# Rev_B.net
KiCad netlist of a schematic drawn in EAGLE
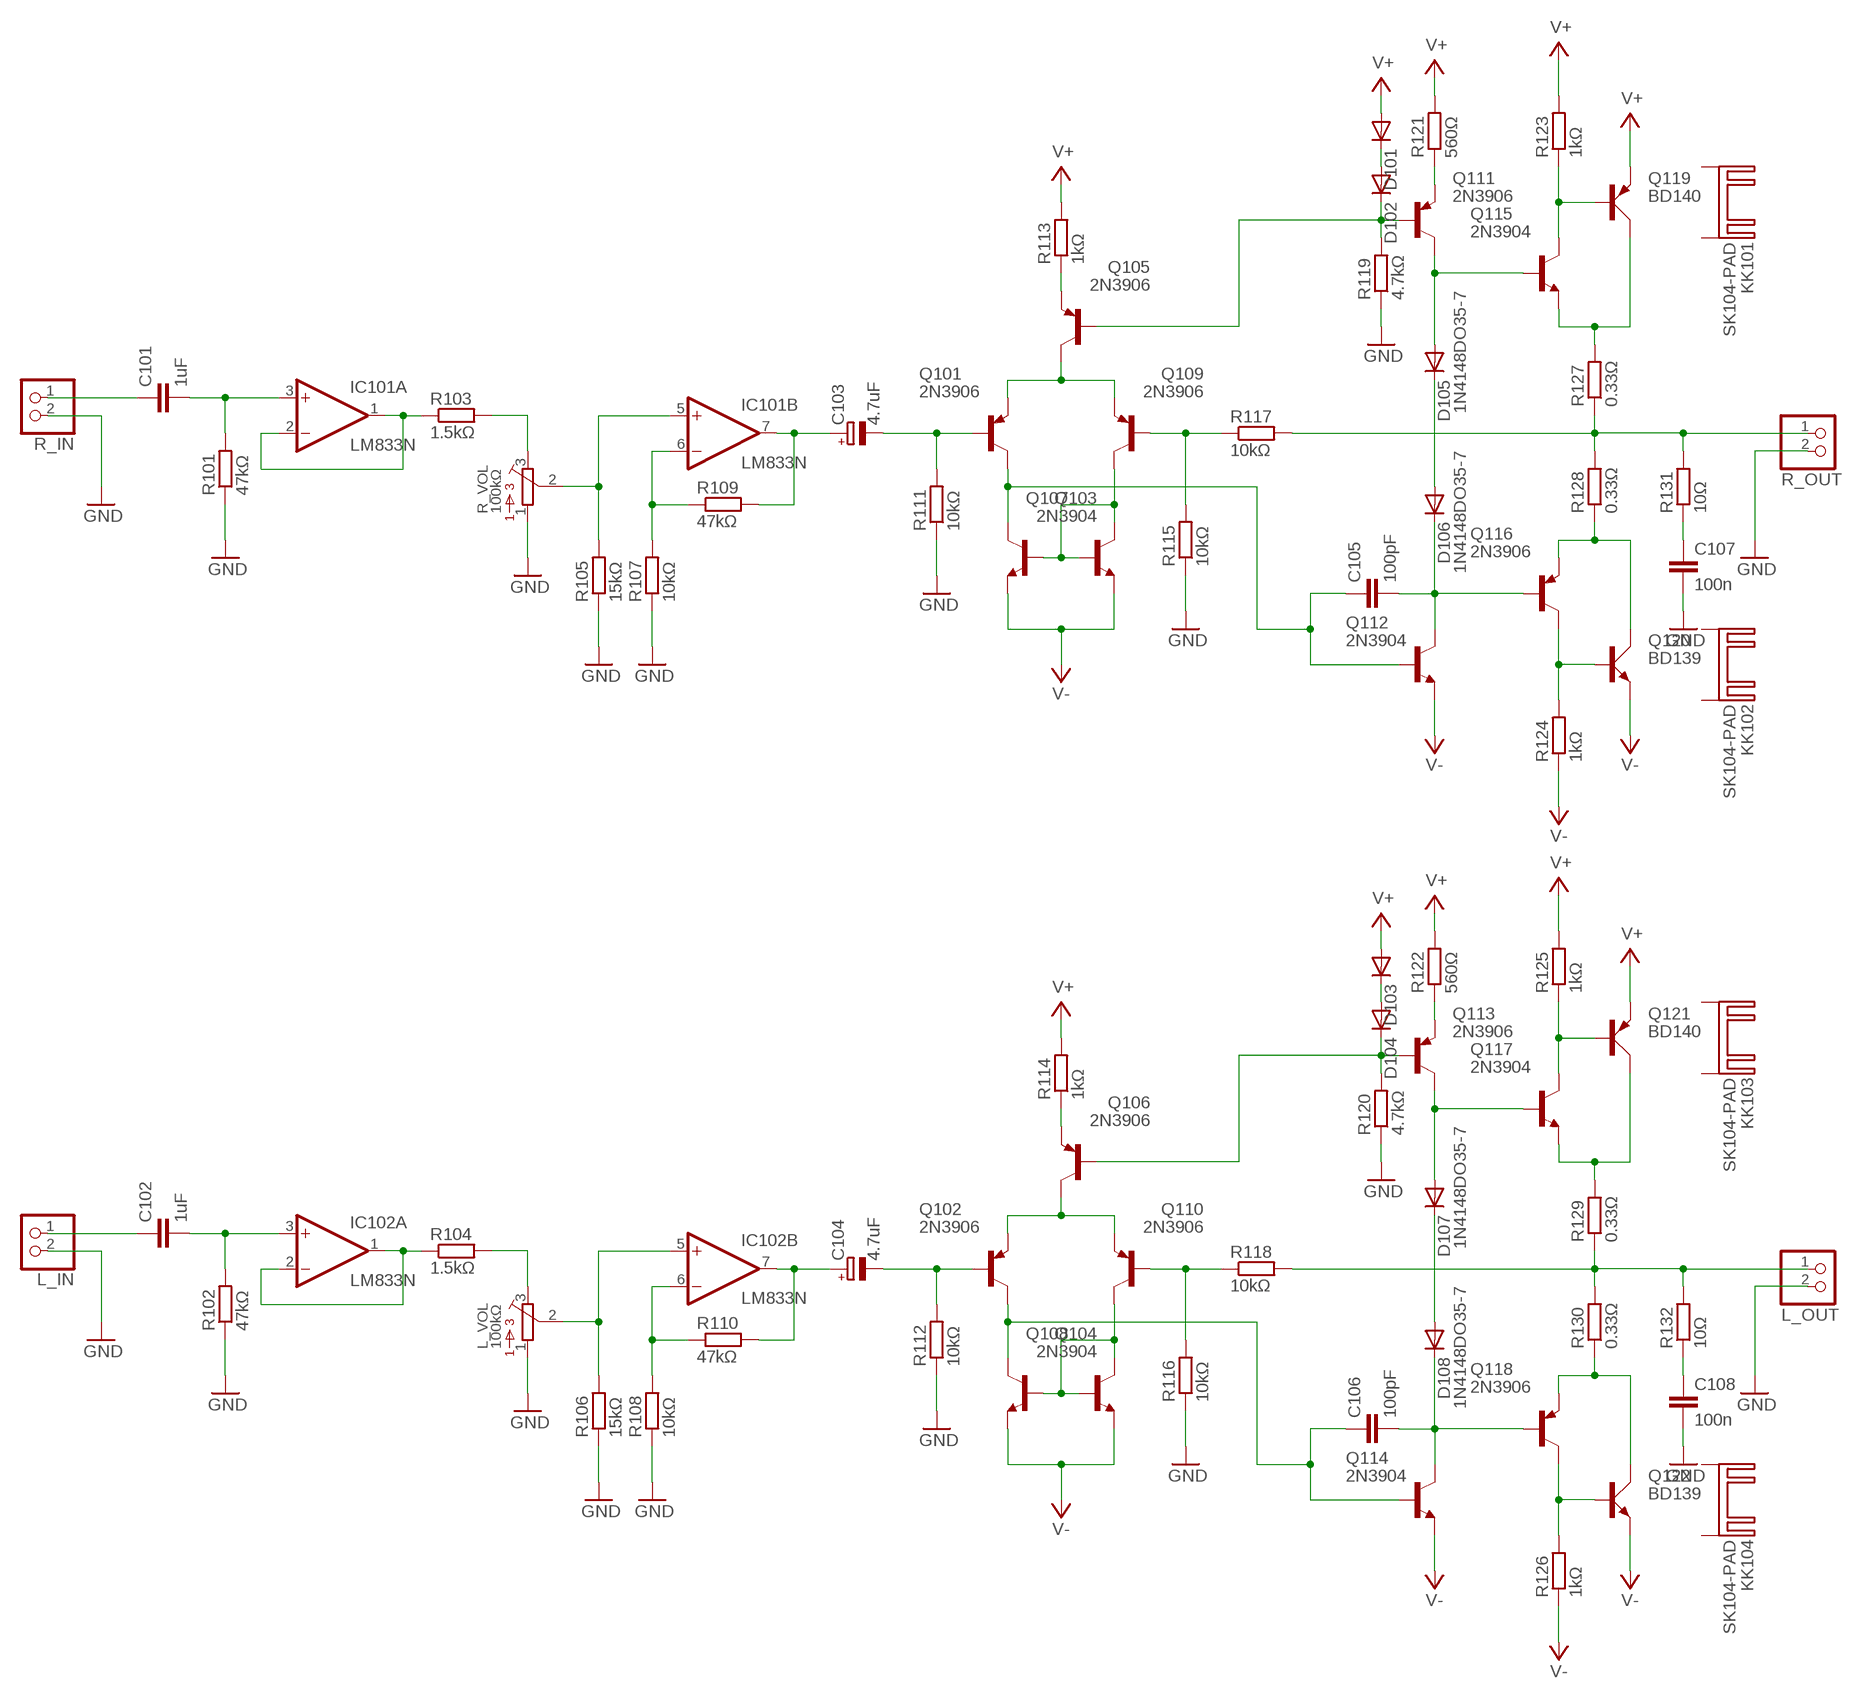
[diagram p0: schematic, sheet 1]
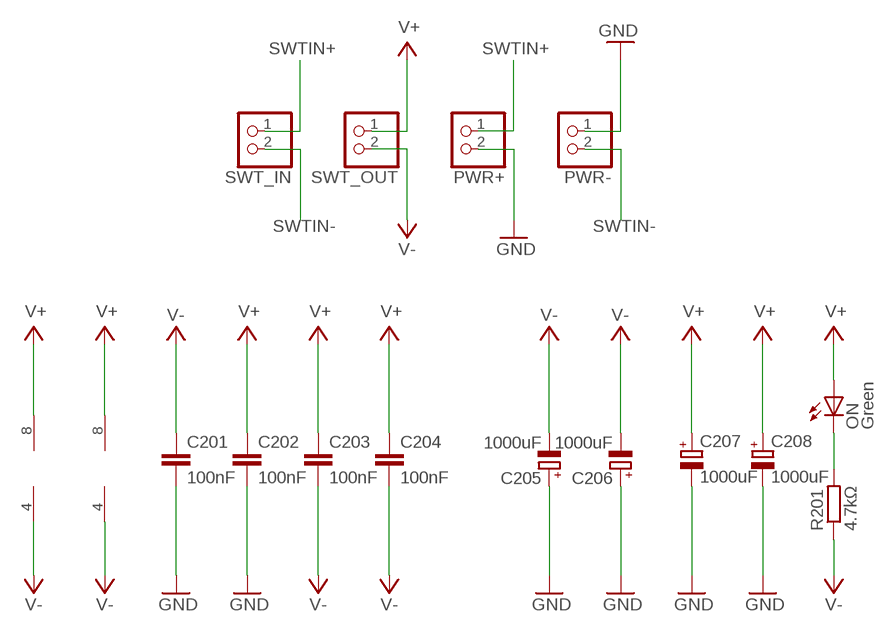
[diagram p1: schematic, sheet 2]

(export (version "E")
  (design (tool "Eeschema 10.0.6"))
  (components
    (comp (ref "C201")
      (value "100nF")
      (footprint "eagle-import:C025-025X050")
      (libsource (lib "eagle-import") (part "C-EU025-025X050"))
    )
    (comp (ref "C202")
      (value "100nF")
      (footprint "eagle-import:C025-025X050")
      (libsource (lib "eagle-import") (part "C-EU025-025X050"))
    )
    (comp (ref "C203")
      (value "100nF")
      (footprint "eagle-import:C025-025X050")
      (libsource (lib "eagle-import") (part "C-EU025-025X050"))
    )
    (comp (ref "C204")
      (value "100nF")
      (footprint "eagle-import:C025-025X050")
      (libsource (lib "eagle-import") (part "C-EU025-025X050"))
    )
    (comp (ref "C205")
      (value "1000uF")
      (footprint "eagle-import:E5-10,5")
      (libsource (lib "eagle-import") (part "CPOL-EUE5-10.5"))
    )
    (comp (ref "C206")
      (value "1000uF")
      (footprint "eagle-import:E5-10,5")
      (libsource (lib "eagle-import") (part "CPOL-EUE5-10.5"))
    )
    (comp (ref "C207")
      (value "1000uF")
      (footprint "eagle-import:E5-10,5")
      (libsource (lib "eagle-import") (part "CPOL-EUE5-10.5"))
    )
    (comp (ref "C208")
      (value "1000uF")
      (footprint "eagle-import:E5-10,5")
      (libsource (lib "eagle-import") (part "CPOL-EUE5-10.5"))
    )
    (comp (ref "IC101")
      (value "LM833N")
      (footprint "eagle-import:DIL08")
      (libsource (lib "eagle-import") (part "LM833N"))
    )
    (comp (ref "IC102")
      (value "LM833N")
      (footprint "eagle-import:DIL08")
      (libsource (lib "eagle-import") (part "LM833N"))
    )
    (comp (ref "ON")
      (value "Green")
      (footprint "eagle-import:LED5MM")
      (libsource (lib "eagle-import") (part "LED5MM"))
    )
    (comp (ref "PWR+")
      (value "JST_2PIN-THM")
      (footprint "eagle-import:JST-PH-2-THM")
      (libsource (lib "eagle-import") (part "JST_2PIN-THM"))
    )
    (comp (ref "PWR-")
      (value "JST_2PIN-THM")
      (footprint "eagle-import:JST-PH-2-THM")
      (libsource (lib "eagle-import") (part "JST_2PIN-THM"))
    )
    (comp (ref "R201")
      (value "4.7kΩ")
      (footprint "eagle-import:0207_10")
      (libsource (lib "eagle-import") (part "R-EU_0207/10"))
    )
    (comp (ref "SWT_IN")
      (value "JST_2PIN-THM")
      (footprint "eagle-import:JST-PH-2-THM")
      (libsource (lib "eagle-import") (part "JST_2PIN-THM"))
    )
    (comp (ref "SWT_OUT")
      (value "JST_2PIN-THM")
      (footprint "eagle-import:JST-PH-2-THM")
      (libsource (lib "eagle-import") (part "JST_2PIN-THM"))
    )
    (comp (ref "C101")
      (value "1uF")
      (footprint "eagle-import:C150-072X183")
      (libsource (lib "eagle-import") (part "C-EU150-072X183"))
    )
    (comp (ref "C102")
      (value "1uF")
      (footprint "eagle-import:C150-072X183")
      (libsource (lib "eagle-import") (part "C-EU150-072X183"))
    )
    (comp (ref "C103")
      (value "4.7uF")
      (footprint "eagle-import:E2-5")
      (libsource (lib "eagle-import") (part "CPOL-EUE2-5"))
    )
    (comp (ref "C104")
      (value "4.7uF")
      (footprint "eagle-import:E2-5")
      (libsource (lib "eagle-import") (part "CPOL-EUE2-5"))
    )
    (comp (ref "C105")
      (value "100pF")
      (footprint "eagle-import:C050-050X075")
      (libsource (lib "eagle-import") (part "C-EU050-050X075"))
    )
    (comp (ref "C106")
      (value "100pF")
      (footprint "eagle-import:C050-050X075")
      (libsource (lib "eagle-import") (part "C-EU050-050X075"))
    )
    (comp (ref "C107")
      (value "100n")
      (footprint "eagle-import:C075-042X103")
      (libsource (lib "eagle-import") (part "C-EU075-042X103"))
    )
    (comp (ref "C108")
      (value "100n")
      (footprint "eagle-import:C075-042X103")
      (libsource (lib "eagle-import") (part "C-EU075-042X103"))
    )
    (comp (ref "D101")
      (value "1N4148DO35-7")
      (footprint "eagle-import:DO35-7")
      (libsource (lib "eagle-import") (part "1N4148DO35-7"))
    )
    (comp (ref "D102")
      (value "1N4148DO35-7")
      (footprint "eagle-import:DO35-7")
      (libsource (lib "eagle-import") (part "1N4148DO35-7"))
    )
    (comp (ref "D103")
      (value "1N4148DO35-7")
      (footprint "eagle-import:DO35-7")
      (libsource (lib "eagle-import") (part "1N4148DO35-7"))
    )
    (comp (ref "D104")
      (value "1N4148DO35-7")
      (footprint "eagle-import:DO35-7")
      (libsource (lib "eagle-import") (part "1N4148DO35-7"))
    )
    (comp (ref "D105")
      (value "1N4148DO35-7")
      (footprint "eagle-import:DO35-7")
      (libsource (lib "eagle-import") (part "1N4148DO35-7"))
    )
    (comp (ref "D106")
      (value "1N4148DO35-7")
      (footprint "eagle-import:DO35-7")
      (libsource (lib "eagle-import") (part "1N4148DO35-7"))
    )
    (comp (ref "D107")
      (value "1N4148DO35-7")
      (footprint "eagle-import:DO35-7")
      (libsource (lib "eagle-import") (part "1N4148DO35-7"))
    )
    (comp (ref "D108")
      (value "1N4148DO35-7")
      (footprint "eagle-import:DO35-7")
      (libsource (lib "eagle-import") (part "1N4148DO35-7"))
    )
    (comp (ref "KK101")
      (value "SK104-PAD")
      (footprint "eagle-import:SK104-PAD")
      (libsource (lib "eagle-import") (part "SK104-PAD"))
    )
    (comp (ref "KK102")
      (value "SK104-PAD")
      (footprint "eagle-import:SK104-PAD")
      (libsource (lib "eagle-import") (part "SK104-PAD"))
    )
    (comp (ref "KK103")
      (value "SK104-PAD")
      (footprint "eagle-import:SK104-PAD")
      (libsource (lib "eagle-import") (part "SK104-PAD"))
    )
    (comp (ref "KK104")
      (value "SK104-PAD")
      (footprint "eagle-import:SK104-PAD")
      (libsource (lib "eagle-import") (part "SK104-PAD"))
    )
    (comp (ref "L_IN")
      (value "JST_2PIN-THM")
      (footprint "eagle-import:JST-PH-2-THM")
      (libsource (lib "eagle-import") (part "JST_2PIN-THM"))
    )
    (comp (ref "L_OUT")
      (value "JST_2PIN-THM")
      (footprint "eagle-import:JST-PH-2-THM")
      (libsource (lib "eagle-import") (part "JST_2PIN-THM"))
    )
    (comp (ref "L_VOL")
      (value "100kΩ")
      (footprint "eagle-import:3362U")
      (libsource (lib "eagle-import") (part "3362U"))
    )
    (comp (ref "Q101")
      (value "2N3906")
      (footprint "eagle-import:TO92")
      (libsource (lib "eagle-import") (part "2N3906"))
    )
    (comp (ref "Q102")
      (value "2N3906")
      (footprint "eagle-import:TO92")
      (libsource (lib "eagle-import") (part "2N3906"))
    )
    (comp (ref "Q103")
      (value "2N3904")
      (footprint "eagle-import:TO92")
      (libsource (lib "eagle-import") (part "2N3904"))
    )
    (comp (ref "Q104")
      (value "2N3904")
      (footprint "eagle-import:TO92")
      (libsource (lib "eagle-import") (part "2N3904"))
    )
    (comp (ref "Q105")
      (value "2N3906")
      (footprint "eagle-import:TO92")
      (libsource (lib "eagle-import") (part "2N3906"))
    )
    (comp (ref "Q106")
      (value "2N3906")
      (footprint "eagle-import:TO92")
      (libsource (lib "eagle-import") (part "2N3906"))
    )
    (comp (ref "Q107")
      (value "2N3904")
      (footprint "eagle-import:TO92")
      (libsource (lib "eagle-import") (part "2N3904"))
    )
    (comp (ref "Q108")
      (value "2N3904")
      (footprint "eagle-import:TO92")
      (libsource (lib "eagle-import") (part "2N3904"))
    )
    (comp (ref "Q109")
      (value "2N3906")
      (footprint "eagle-import:TO92")
      (libsource (lib "eagle-import") (part "2N3906"))
    )
    (comp (ref "Q110")
      (value "2N3906")
      (footprint "eagle-import:TO92")
      (libsource (lib "eagle-import") (part "2N3906"))
    )
    (comp (ref "Q111")
      (value "2N3906")
      (footprint "eagle-import:TO92")
      (libsource (lib "eagle-import") (part "2N3906"))
    )
    (comp (ref "Q112")
      (value "2N3904")
      (footprint "eagle-import:TO92")
      (libsource (lib "eagle-import") (part "2N3904"))
    )
    (comp (ref "Q113")
      (value "2N3906")
      (footprint "eagle-import:TO92")
      (libsource (lib "eagle-import") (part "2N3906"))
    )
    (comp (ref "Q114")
      (value "2N3904")
      (footprint "eagle-import:TO92")
      (libsource (lib "eagle-import") (part "2N3904"))
    )
    (comp (ref "Q115")
      (value "2N3904")
      (footprint "eagle-import:TO92")
      (libsource (lib "eagle-import") (part "2N3904"))
    )
    (comp (ref "Q116")
      (value "2N3906")
      (footprint "eagle-import:TO92")
      (libsource (lib "eagle-import") (part "2N3906"))
    )
    (comp (ref "Q117")
      (value "2N3904")
      (footprint "eagle-import:TO92")
      (libsource (lib "eagle-import") (part "2N3904"))
    )
    (comp (ref "Q118")
      (value "2N3906")
      (footprint "eagle-import:TO92")
      (libsource (lib "eagle-import") (part "2N3906"))
    )
    (comp (ref "Q119")
      (value "BD140")
      (footprint "eagle-import:TO126AV")
      (libsource (lib "eagle-import") (part "BD140"))
    )
    (comp (ref "Q120")
      (value "BD139")
      (footprint "eagle-import:TO126AV")
      (libsource (lib "eagle-import") (part "BD139"))
    )
    (comp (ref "Q121")
      (value "BD140")
      (footprint "eagle-import:TO126AV")
      (libsource (lib "eagle-import") (part "BD140"))
    )
    (comp (ref "Q122")
      (value "BD139")
      (footprint "eagle-import:TO126AV")
      (libsource (lib "eagle-import") (part "BD139"))
    )
    (comp (ref "R101")
      (value "47kΩ")
      (footprint "eagle-import:0207_10")
      (libsource (lib "eagle-import") (part "R-EU_0207/10"))
    )
    (comp (ref "R102")
      (value "47kΩ")
      (footprint "eagle-import:0207_10")
      (libsource (lib "eagle-import") (part "R-EU_0207/10"))
    )
    (comp (ref "R103")
      (value "1.5kΩ")
      (footprint "eagle-import:0207_10")
      (libsource (lib "eagle-import") (part "R-EU_0207/10"))
    )
    (comp (ref "R104")
      (value "1.5kΩ")
      (footprint "eagle-import:0207_10")
      (libsource (lib "eagle-import") (part "R-EU_0207/10"))
    )
    (comp (ref "R105")
      (value "15kΩ")
      (footprint "eagle-import:0207_10")
      (libsource (lib "eagle-import") (part "R-EU_0207/10"))
    )
    (comp (ref "R106")
      (value "15kΩ")
      (footprint "eagle-import:0207_10")
      (libsource (lib "eagle-import") (part "R-EU_0207/10"))
    )
    (comp (ref "R107")
      (value "10kΩ")
      (footprint "eagle-import:0207_10")
      (libsource (lib "eagle-import") (part "R-EU_0207/10"))
    )
    (comp (ref "R108")
      (value "10kΩ")
      (footprint "eagle-import:0207_10")
      (libsource (lib "eagle-import") (part "R-EU_0207/10"))
    )
    (comp (ref "R109")
      (value "47kΩ")
      (footprint "eagle-import:0207_10")
      (libsource (lib "eagle-import") (part "R-EU_0207/10"))
    )
    (comp (ref "R110")
      (value "47kΩ")
      (footprint "eagle-import:0207_10")
      (libsource (lib "eagle-import") (part "R-EU_0207/10"))
    )
    (comp (ref "R111")
      (value "10kΩ")
      (footprint "eagle-import:0207_10")
      (libsource (lib "eagle-import") (part "R-EU_0207/10"))
    )
    (comp (ref "R112")
      (value "10kΩ")
      (footprint "eagle-import:0207_10")
      (libsource (lib "eagle-import") (part "R-EU_0207/10"))
    )
    (comp (ref "R113")
      (value "1kΩ")
      (footprint "eagle-import:0207_10")
      (libsource (lib "eagle-import") (part "R-EU_0207/10"))
    )
    (comp (ref "R114")
      (value "1kΩ")
      (footprint "eagle-import:0207_10")
      (libsource (lib "eagle-import") (part "R-EU_0207/10"))
    )
    (comp (ref "R115")
      (value "10kΩ")
      (footprint "eagle-import:0207_10")
      (libsource (lib "eagle-import") (part "R-EU_0207/10"))
    )
    (comp (ref "R116")
      (value "10kΩ")
      (footprint "eagle-import:0207_10")
      (libsource (lib "eagle-import") (part "R-EU_0207/10"))
    )
    (comp (ref "R117")
      (value "10kΩ")
      (footprint "eagle-import:0207_10")
      (libsource (lib "eagle-import") (part "R-EU_0207/10"))
    )
    (comp (ref "R118")
      (value "10kΩ")
      (footprint "eagle-import:0207_10")
      (libsource (lib "eagle-import") (part "R-EU_0207/10"))
    )
    (comp (ref "R119")
      (value "4.7kΩ")
      (footprint "eagle-import:0207_10")
      (libsource (lib "eagle-import") (part "R-EU_0207/10"))
    )
    (comp (ref "R120")
      (value "4.7kΩ")
      (footprint "eagle-import:0207_10")
      (libsource (lib "eagle-import") (part "R-EU_0207/10"))
    )
    (comp (ref "R121")
      (value "560Ω")
      (footprint "eagle-import:0207_10")
      (libsource (lib "eagle-import") (part "R-EU_0207/10"))
    )
    (comp (ref "R122")
      (value "560Ω")
      (footprint "eagle-import:0207_10")
      (libsource (lib "eagle-import") (part "R-EU_0207/10"))
    )
    (comp (ref "R123")
      (value "1kΩ")
      (footprint "eagle-import:0207_10")
      (libsource (lib "eagle-import") (part "R-EU_0207/10"))
    )
    (comp (ref "R124")
      (value "1kΩ")
      (footprint "eagle-import:0207_10")
      (libsource (lib "eagle-import") (part "R-EU_0207/10"))
    )
    (comp (ref "R125")
      (value "1kΩ")
      (footprint "eagle-import:0207_10")
      (libsource (lib "eagle-import") (part "R-EU_0207/10"))
    )
    (comp (ref "R126")
      (value "1kΩ")
      (footprint "eagle-import:0207_10")
      (libsource (lib "eagle-import") (part "R-EU_0207/10"))
    )
    (comp (ref "R127")
      (value "0.33Ω")
      (footprint "eagle-import:0309_12")
      (libsource (lib "eagle-import") (part "R-EU_0309/12"))
    )
    (comp (ref "R128")
      (value "0.33Ω")
      (footprint "eagle-import:0309_12")
      (libsource (lib "eagle-import") (part "R-EU_0309/12"))
    )
    (comp (ref "R129")
      (value "0.33Ω")
      (footprint "eagle-import:0309_12")
      (libsource (lib "eagle-import") (part "R-EU_0309/12"))
    )
    (comp (ref "R130")
      (value "0.33Ω")
      (footprint "eagle-import:0309_12")
      (libsource (lib "eagle-import") (part "R-EU_0309/12"))
    )
    (comp (ref "R131")
      (value "10Ω")
      (footprint "eagle-import:0617V")
      (libsource (lib "eagle-import") (part "R-EU_0617/5V"))
    )
    (comp (ref "R132")
      (value "10Ω")
      (footprint "eagle-import:0617V")
      (libsource (lib "eagle-import") (part "R-EU_0617/5V"))
    )
    (comp (ref "R_IN")
      (value "JST_2PIN-THM")
      (footprint "eagle-import:JST-PH-2-THM")
      (libsource (lib "eagle-import") (part "JST_2PIN-THM"))
    )
    (comp (ref "R_OUT")
      (value "JST_2PIN-THM")
      (footprint "eagle-import:JST-PH-2-THM")
      (libsource (lib "eagle-import") (part "JST_2PIN-THM"))
    )
    (comp (ref "R_VOL")
      (value "100kΩ")
      (footprint "eagle-import:3362U")
      (libsource (lib "eagle-import") (part "3362U"))
    )
  )
  (nets
    (net (code "1") (name "GND") (class "Default")
      (node (ref "C107") (pin "2") (pinfunction "2_2") (pintype "passive"))
      (node (ref "C108") (pin "2") (pinfunction "2_2") (pintype "passive"))
      (node (ref "C201") (pin "2") (pinfunction "2_2") (pintype "passive"))
      (node (ref "C202") (pin "2") (pinfunction "2_2") (pintype "passive"))
      (node (ref "C205") (pin "+") (pinfunction "+_+") (pintype "passive"))
      (node (ref "C206") (pin "+") (pinfunction "+_+") (pintype "passive"))
      (node (ref "C207") (pin "-") (pinfunction "-_-") (pintype "passive"))
      (node (ref "C208") (pin "-") (pinfunction "-_-") (pintype "passive"))
      (node (ref "L_IN") (pin "2") (pinfunction "1_2") (pintype "passive"))
      (node (ref "L_OUT") (pin "2") (pinfunction "1_2") (pintype "passive"))
      (node (ref "L_VOL") (pin "1") (pinfunction "1_1") (pintype "passive"))
      (node (ref "PWR+") (pin "2") (pinfunction "1_2") (pintype "passive"))
      (node (ref "PWR-") (pin "1") (pinfunction "2_1") (pintype "passive"))
      (node (ref "R101") (pin "1") (pinfunction "1_1") (pintype "passive"))
      (node (ref "R102") (pin "1") (pinfunction "1_1") (pintype "passive"))
      (node (ref "R105") (pin "1") (pinfunction "1_1") (pintype "passive"))
      (node (ref "R106") (pin "1") (pinfunction "1_1") (pintype "passive"))
      (node (ref "R107") (pin "1") (pinfunction "1_1") (pintype "passive"))
      (node (ref "R108") (pin "1") (pinfunction "1_1") (pintype "passive"))
      (node (ref "R111") (pin "1") (pinfunction "1_1") (pintype "passive"))
      (node (ref "R112") (pin "1") (pinfunction "1_1") (pintype "passive"))
      (node (ref "R115") (pin "1") (pinfunction "1_1") (pintype "passive"))
      (node (ref "R116") (pin "1") (pinfunction "1_1") (pintype "passive"))
      (node (ref "R119") (pin "1") (pinfunction "1_1") (pintype "passive"))
      (node (ref "R120") (pin "1") (pinfunction "1_1") (pintype "passive"))
      (node (ref "R_IN") (pin "2") (pinfunction "1_2") (pintype "passive"))
      (node (ref "R_OUT") (pin "2") (pinfunction "1_2") (pintype "passive"))
      (node (ref "R_VOL") (pin "1") (pinfunction "1_1") (pintype "passive"))
    )
    (net (code "2") (name "Net-(C107-Pad1)") (class "Default")
      (node (ref "C107") (pin "1") (pinfunction "1_1") (pintype "passive"))
      (node (ref "R131") (pin "1") (pinfunction "1_1") (pintype "passive"))
    )
    (net (code "3") (name "Net-(C108-Pad1)") (class "Default")
      (node (ref "C108") (pin "1") (pinfunction "1_1") (pintype "passive"))
      (node (ref "R132") (pin "1") (pinfunction "1_1") (pintype "passive"))
    )
    (net (code "4") (name "Net-(D101-PadC)") (class "Default")
      (node (ref "D101") (pin "C") (pinfunction "C_C") (pintype "passive"))
      (node (ref "D102") (pin "A") (pinfunction "A_A") (pintype "passive"))
    )
    (net (code "5") (name "Net-(D103-PadC)") (class "Default")
      (node (ref "D103") (pin "C") (pinfunction "C_C") (pintype "passive"))
      (node (ref "D104") (pin "A") (pinfunction "A_A") (pintype "passive"))
    )
    (net (code "6") (name "Net-(D105-PadC)") (class "Default")
      (node (ref "D105") (pin "C") (pinfunction "C_C") (pintype "passive"))
      (node (ref "D106") (pin "A") (pinfunction "A_A") (pintype "passive"))
    )
    (net (code "7") (name "Net-(D107-PadC)") (class "Default")
      (node (ref "D107") (pin "C") (pinfunction "C_C") (pintype "passive"))
      (node (ref "D108") (pin "A") (pinfunction "A_A") (pintype "passive"))
    )
    (net (code "8") (name "Net-(IC101A-+IN)") (class "Default")
      (node (ref "C101") (pin "2") (pinfunction "2_2") (pintype "passive"))
      (node (ref "IC101") (pin "3") (pinfunction "+IN_3") (pintype "input"))
      (node (ref "R101") (pin "2") (pinfunction "2_2") (pintype "passive"))
    )
    (net (code "9") (name "Net-(IC101A--IN)") (class "Default")
      (node (ref "IC101") (pin "1") (pinfunction "OUT_1") (pintype "output"))
      (node (ref "IC101") (pin "2") (pinfunction "-IN_2") (pintype "input"))
      (node (ref "R103") (pin "1") (pinfunction "1_1") (pintype "passive"))
    )
    (net (code "10") (name "Net-(IC101B-+IN)") (class "Default")
      (node (ref "IC101") (pin "5") (pinfunction "+IN_5") (pintype "input"))
      (node (ref "R105") (pin "2") (pinfunction "2_2") (pintype "passive"))
      (node (ref "R_VOL") (pin "2") (pinfunction "2_2") (pintype "passive"))
    )
    (net (code "11") (name "Net-(IC101B--IN)") (class "Default")
      (node (ref "IC101") (pin "6") (pinfunction "-IN_6") (pintype "input"))
      (node (ref "R107") (pin "2") (pinfunction "2_2") (pintype "passive"))
      (node (ref "R109") (pin "1") (pinfunction "1_1") (pintype "passive"))
    )
    (net (code "12") (name "Net-(IC101B-OUT)") (class "Default")
      (node (ref "C103") (pin "+") (pinfunction "+_+") (pintype "passive"))
      (node (ref "IC101") (pin "7") (pinfunction "OUT_7") (pintype "output"))
      (node (ref "R109") (pin "2") (pinfunction "2_2") (pintype "passive"))
    )
    (net (code "13") (name "Net-(IC102A-+IN)") (class "Default")
      (node (ref "C102") (pin "2") (pinfunction "2_2") (pintype "passive"))
      (node (ref "IC102") (pin "3") (pinfunction "+IN_3") (pintype "input"))
      (node (ref "R102") (pin "2") (pinfunction "2_2") (pintype "passive"))
    )
    (net (code "14") (name "Net-(IC102A--IN)") (class "Default")
      (node (ref "IC102") (pin "1") (pinfunction "OUT_1") (pintype "output"))
      (node (ref "IC102") (pin "2") (pinfunction "-IN_2") (pintype "input"))
      (node (ref "R104") (pin "1") (pinfunction "1_1") (pintype "passive"))
    )
    (net (code "15") (name "Net-(IC102B-+IN)") (class "Default")
      (node (ref "IC102") (pin "5") (pinfunction "+IN_5") (pintype "input"))
      (node (ref "L_VOL") (pin "2") (pinfunction "2_2") (pintype "passive"))
      (node (ref "R106") (pin "2") (pinfunction "2_2") (pintype "passive"))
    )
    (net (code "16") (name "Net-(IC102B--IN)") (class "Default")
      (node (ref "IC102") (pin "6") (pinfunction "-IN_6") (pintype "input"))
      (node (ref "R108") (pin "2") (pinfunction "2_2") (pintype "passive"))
      (node (ref "R110") (pin "1") (pinfunction "1_1") (pintype "passive"))
    )
    (net (code "17") (name "Net-(IC102B-OUT)") (class "Default")
      (node (ref "C104") (pin "+") (pinfunction "+_+") (pintype "passive"))
      (node (ref "IC102") (pin "7") (pinfunction "OUT_7") (pintype "output"))
      (node (ref "R110") (pin "2") (pinfunction "2_2") (pintype "passive"))
    )
    (net (code "18") (name "Net-(L_IN-2)") (class "Default")
      (node (ref "C102") (pin "1") (pinfunction "1_1") (pintype "passive"))
      (node (ref "L_IN") (pin "1") (pinfunction "2_1") (pintype "passive"))
    )
    (net (code "19") (name "Net-(L_OUT-2)") (class "Default")
      (node (ref "L_OUT") (pin "1") (pinfunction "2_1") (pintype "passive"))
      (node (ref "R118") (pin "2") (pinfunction "2_2") (pintype "passive"))
      (node (ref "R129") (pin "1") (pinfunction "1_1") (pintype "passive"))
      (node (ref "R130") (pin "2") (pinfunction "2_2") (pintype "passive"))
      (node (ref "R132") (pin "2") (pinfunction "2_2") (pintype "passive"))
    )
    (net (code "20") (name "Net-(L_VOL-Pad3)") (class "Default")
      (node (ref "L_VOL") (pin "3") (pinfunction "3_3") (pintype "passive"))
      (node (ref "R104") (pin "2") (pinfunction "2_2") (pintype "passive"))
    )
    (net (code "21") (name "Net-(ON-C)") (class "Default")
      (node (ref "ON") (pin "K") (pinfunction "C_K") (pintype "passive"))
      (node (ref "R201") (pin "2") (pinfunction "2_2") (pintype "passive"))
    )
    (net (code "22") (name "Net-(Q101-B)") (class "Default")
      (node (ref "C103") (pin "-") (pinfunction "-_-") (pintype "passive"))
      (node (ref "Q101") (pin "2") (pinfunction "B_2") (pintype "passive"))
      (node (ref "R111") (pin "2") (pinfunction "2_2") (pintype "passive"))
    )
    (net (code "23") (name "Net-(Q101-C)") (class "Default")
      (node (ref "C105") (pin "1") (pinfunction "1_1") (pintype "passive"))
      (node (ref "Q101") (pin "1") (pinfunction "C_1") (pintype "passive"))
      (node (ref "Q103") (pin "1") (pinfunction "C_1") (pintype "passive"))
      (node (ref "Q112") (pin "2") (pinfunction "B_2") (pintype "passive"))
    )
    (net (code "24") (name "Net-(Q101-E)") (class "Default")
      (node (ref "Q101") (pin "3") (pinfunction "E_3") (pintype "passive"))
      (node (ref "Q105") (pin "1") (pinfunction "C_1") (pintype "passive"))
      (node (ref "Q109") (pin "3") (pinfunction "E_3") (pintype "passive"))
    )
    (net (code "25") (name "Net-(Q102-B)") (class "Default")
      (node (ref "C104") (pin "-") (pinfunction "-_-") (pintype "passive"))
      (node (ref "Q102") (pin "2") (pinfunction "B_2") (pintype "passive"))
      (node (ref "R112") (pin "2") (pinfunction "2_2") (pintype "passive"))
    )
    (net (code "26") (name "Net-(Q102-C)") (class "Default")
      (node (ref "C106") (pin "1") (pinfunction "1_1") (pintype "passive"))
      (node (ref "Q102") (pin "1") (pinfunction "C_1") (pintype "passive"))
      (node (ref "Q104") (pin "1") (pinfunction "C_1") (pintype "passive"))
      (node (ref "Q114") (pin "2") (pinfunction "B_2") (pintype "passive"))
    )
    (net (code "27") (name "Net-(Q102-E)") (class "Default")
      (node (ref "Q102") (pin "3") (pinfunction "E_3") (pintype "passive"))
      (node (ref "Q106") (pin "1") (pinfunction "C_1") (pintype "passive"))
      (node (ref "Q110") (pin "3") (pinfunction "E_3") (pintype "passive"))
    )
    (net (code "28") (name "Net-(Q103-B)") (class "Default")
      (node (ref "Q103") (pin "2") (pinfunction "B_2") (pintype "passive"))
      (node (ref "Q107") (pin "1") (pinfunction "C_1") (pintype "passive"))
      (node (ref "Q107") (pin "2") (pinfunction "B_2") (pintype "passive"))
      (node (ref "Q109") (pin "1") (pinfunction "C_1") (pintype "passive"))
    )
    (net (code "29") (name "Net-(Q104-B)") (class "Default")
      (node (ref "Q104") (pin "2") (pinfunction "B_2") (pintype "passive"))
      (node (ref "Q108") (pin "1") (pinfunction "C_1") (pintype "passive"))
      (node (ref "Q108") (pin "2") (pinfunction "B_2") (pintype "passive"))
      (node (ref "Q110") (pin "1") (pinfunction "C_1") (pintype "passive"))
    )
    (net (code "30") (name "Net-(Q105-B)") (class "Default")
      (node (ref "D102") (pin "C") (pinfunction "C_C") (pintype "passive"))
      (node (ref "Q105") (pin "2") (pinfunction "B_2") (pintype "passive"))
      (node (ref "Q111") (pin "2") (pinfunction "B_2") (pintype "passive"))
      (node (ref "R119") (pin "2") (pinfunction "2_2") (pintype "passive"))
    )
    (net (code "31") (name "Net-(Q105-E)") (class "Default")
      (node (ref "Q105") (pin "3") (pinfunction "E_3") (pintype "passive"))
      (node (ref "R113") (pin "1") (pinfunction "1_1") (pintype "passive"))
    )
    (net (code "32") (name "Net-(Q106-B)") (class "Default")
      (node (ref "D104") (pin "C") (pinfunction "C_C") (pintype "passive"))
      (node (ref "Q106") (pin "2") (pinfunction "B_2") (pintype "passive"))
      (node (ref "Q113") (pin "2") (pinfunction "B_2") (pintype "passive"))
      (node (ref "R120") (pin "2") (pinfunction "2_2") (pintype "passive"))
    )
    (net (code "33") (name "Net-(Q106-E)") (class "Default")
      (node (ref "Q106") (pin "3") (pinfunction "E_3") (pintype "passive"))
      (node (ref "R114") (pin "1") (pinfunction "1_1") (pintype "passive"))
    )
    (net (code "34") (name "Net-(Q109-B)") (class "Default")
      (node (ref "Q109") (pin "2") (pinfunction "B_2") (pintype "passive"))
      (node (ref "R115") (pin "2") (pinfunction "2_2") (pintype "passive"))
      (node (ref "R117") (pin "1") (pinfunction "1_1") (pintype "passive"))
    )
    (net (code "35") (name "Net-(Q110-B)") (class "Default")
      (node (ref "Q110") (pin "2") (pinfunction "B_2") (pintype "passive"))
      (node (ref "R116") (pin "2") (pinfunction "2_2") (pintype "passive"))
      (node (ref "R118") (pin "1") (pinfunction "1_1") (pintype "passive"))
    )
    (net (code "36") (name "Net-(Q111-C)") (class "Default")
      (node (ref "D105") (pin "A") (pinfunction "A_A") (pintype "passive"))
      (node (ref "Q111") (pin "1") (pinfunction "C_1") (pintype "passive"))
      (node (ref "Q115") (pin "2") (pinfunction "B_2") (pintype "passive"))
    )
    (net (code "37") (name "Net-(Q111-E)") (class "Default")
      (node (ref "Q111") (pin "3") (pinfunction "E_3") (pintype "passive"))
      (node (ref "R121") (pin "1") (pinfunction "1_1") (pintype "passive"))
    )
    (net (code "38") (name "Net-(Q112-C)") (class "Default")
      (node (ref "C105") (pin "2") (pinfunction "2_2") (pintype "passive"))
      (node (ref "D106") (pin "C") (pinfunction "C_C") (pintype "passive"))
      (node (ref "Q112") (pin "1") (pinfunction "C_1") (pintype "passive"))
      (node (ref "Q116") (pin "2") (pinfunction "B_2") (pintype "passive"))
    )
    (net (code "39") (name "Net-(Q113-C)") (class "Default")
      (node (ref "D107") (pin "A") (pinfunction "A_A") (pintype "passive"))
      (node (ref "Q113") (pin "1") (pinfunction "C_1") (pintype "passive"))
      (node (ref "Q117") (pin "2") (pinfunction "B_2") (pintype "passive"))
    )
    (net (code "40") (name "Net-(Q113-E)") (class "Default")
      (node (ref "Q113") (pin "3") (pinfunction "E_3") (pintype "passive"))
      (node (ref "R122") (pin "1") (pinfunction "1_1") (pintype "passive"))
    )
    (net (code "41") (name "Net-(Q114-C)") (class "Default")
      (node (ref "C106") (pin "2") (pinfunction "2_2") (pintype "passive"))
      (node (ref "D108") (pin "C") (pinfunction "C_C") (pintype "passive"))
      (node (ref "Q114") (pin "1") (pinfunction "C_1") (pintype "passive"))
      (node (ref "Q118") (pin "2") (pinfunction "B_2") (pintype "passive"))
    )
    (net (code "42") (name "Net-(Q115-C)") (class "Default")
      (node (ref "Q115") (pin "1") (pinfunction "C_1") (pintype "passive"))
      (node (ref "Q119") (pin "B") (pinfunction "B_B") (pintype "passive"))
      (node (ref "R123") (pin "1") (pinfunction "1_1") (pintype "passive"))
    )
    (net (code "43") (name "Net-(Q115-E)") (class "Default")
      (node (ref "Q115") (pin "3") (pinfunction "E_3") (pintype "passive"))
      (node (ref "Q119") (pin "C") (pinfunction "C_C") (pintype "passive"))
      (node (ref "R127") (pin "2") (pinfunction "2_2") (pintype "passive"))
    )
    (net (code "44") (name "Net-(Q116-C)") (class "Default")
      (node (ref "Q116") (pin "1") (pinfunction "C_1") (pintype "passive"))
      (node (ref "Q120") (pin "B") (pinfunction "B_B") (pintype "passive"))
      (node (ref "R124") (pin "2") (pinfunction "2_2") (pintype "passive"))
    )
    (net (code "45") (name "Net-(Q116-E)") (class "Default")
      (node (ref "Q116") (pin "3") (pinfunction "E_3") (pintype "passive"))
      (node (ref "Q120") (pin "C") (pinfunction "C_C") (pintype "passive"))
      (node (ref "R128") (pin "1") (pinfunction "1_1") (pintype "passive"))
    )
    (net (code "46") (name "Net-(Q117-C)") (class "Default")
      (node (ref "Q117") (pin "1") (pinfunction "C_1") (pintype "passive"))
      (node (ref "Q121") (pin "B") (pinfunction "B_B") (pintype "passive"))
      (node (ref "R125") (pin "1") (pinfunction "1_1") (pintype "passive"))
    )
    (net (code "47") (name "Net-(Q117-E)") (class "Default")
      (node (ref "Q117") (pin "3") (pinfunction "E_3") (pintype "passive"))
      (node (ref "Q121") (pin "C") (pinfunction "C_C") (pintype "passive"))
      (node (ref "R129") (pin "2") (pinfunction "2_2") (pintype "passive"))
    )
    (net (code "48") (name "Net-(Q118-C)") (class "Default")
      (node (ref "Q118") (pin "1") (pinfunction "C_1") (pintype "passive"))
      (node (ref "Q122") (pin "B") (pinfunction "B_B") (pintype "passive"))
      (node (ref "R126") (pin "2") (pinfunction "2_2") (pintype "passive"))
    )
    (net (code "49") (name "Net-(Q118-E)") (class "Default")
      (node (ref "Q118") (pin "3") (pinfunction "E_3") (pintype "passive"))
      (node (ref "Q122") (pin "C") (pinfunction "C_C") (pintype "passive"))
      (node (ref "R130") (pin "1") (pinfunction "1_1") (pintype "passive"))
    )
    (net (code "50") (name "Net-(R103-Pad2)") (class "Default")
      (node (ref "R103") (pin "2") (pinfunction "2_2") (pintype "passive"))
      (node (ref "R_VOL") (pin "3") (pinfunction "3_3") (pintype "passive"))
    )
    (net (code "51") (name "Net-(R_IN-2)") (class "Default")
      (node (ref "C101") (pin "1") (pinfunction "1_1") (pintype "passive"))
      (node (ref "R_IN") (pin "1") (pinfunction "2_1") (pintype "passive"))
    )
    (net (code "52") (name "Net-(R_OUT-2)") (class "Default")
      (node (ref "R117") (pin "2") (pinfunction "2_2") (pintype "passive"))
      (node (ref "R127") (pin "1") (pinfunction "1_1") (pintype "passive"))
      (node (ref "R128") (pin "2") (pinfunction "2_2") (pintype "passive"))
      (node (ref "R131") (pin "2") (pinfunction "2_2") (pintype "passive"))
      (node (ref "R_OUT") (pin "1") (pinfunction "2_1") (pintype "passive"))
    )
    (net (code "53") (name "SWTIN+") (class "Default")
      (node (ref "PWR+") (pin "1") (pinfunction "2_1") (pintype "passive"))
      (node (ref "SWT_IN") (pin "1") (pinfunction "2_1") (pintype "passive"))
    )
    (net (code "54") (name "SWTIN-") (class "Default")
      (node (ref "PWR-") (pin "2") (pinfunction "1_2") (pintype "passive"))
      (node (ref "SWT_IN") (pin "2") (pinfunction "1_2") (pintype "passive"))
    )
    (net (code "55") (name "V+") (class "Default")
      (node (ref "C202") (pin "1") (pinfunction "1_1") (pintype "passive"))
      (node (ref "C203") (pin "1") (pinfunction "1_1") (pintype "passive"))
      (node (ref "C204") (pin "1") (pinfunction "1_1") (pintype "passive"))
      (node (ref "C207") (pin "+") (pinfunction "+_+") (pintype "passive"))
      (node (ref "C208") (pin "+") (pinfunction "+_+") (pintype "passive"))
      (node (ref "D101") (pin "A") (pinfunction "A_A") (pintype "passive"))
      (node (ref "D103") (pin "A") (pinfunction "A_A") (pintype "passive"))
      (node (ref "IC101") (pin "8") (pinfunction "V+_8") (pintype "power_in"))
      (node (ref "IC102") (pin "8") (pinfunction "V+_8") (pintype "power_in"))
      (node (ref "ON") (pin "A") (pinfunction "A_A") (pintype "passive"))
      (node (ref "Q119") (pin "E") (pinfunction "E_E") (pintype "passive"))
      (node (ref "Q121") (pin "E") (pinfunction "E_E") (pintype "passive"))
      (node (ref "R113") (pin "2") (pinfunction "2_2") (pintype "passive"))
      (node (ref "R114") (pin "2") (pinfunction "2_2") (pintype "passive"))
      (node (ref "R121") (pin "2") (pinfunction "2_2") (pintype "passive"))
      (node (ref "R122") (pin "2") (pinfunction "2_2") (pintype "passive"))
      (node (ref "R123") (pin "2") (pinfunction "2_2") (pintype "passive"))
      (node (ref "R125") (pin "2") (pinfunction "2_2") (pintype "passive"))
      (node (ref "SWT_OUT") (pin "1") (pinfunction "2_1") (pintype "passive"))
    )
    (net (code "56") (name "V-") (class "Default")
      (node (ref "C201") (pin "1") (pinfunction "1_1") (pintype "passive"))
      (node (ref "C203") (pin "2") (pinfunction "2_2") (pintype "passive"))
      (node (ref "C204") (pin "2") (pinfunction "2_2") (pintype "passive"))
      (node (ref "C205") (pin "-") (pinfunction "-_-") (pintype "passive"))
      (node (ref "C206") (pin "-") (pinfunction "-_-") (pintype "passive"))
      (node (ref "IC101") (pin "4") (pinfunction "V-_4") (pintype "power_in"))
      (node (ref "IC102") (pin "4") (pinfunction "V-_4") (pintype "power_in"))
      (node (ref "Q103") (pin "3") (pinfunction "E_3") (pintype "passive"))
      (node (ref "Q104") (pin "3") (pinfunction "E_3") (pintype "passive"))
      (node (ref "Q107") (pin "3") (pinfunction "E_3") (pintype "passive"))
      (node (ref "Q108") (pin "3") (pinfunction "E_3") (pintype "passive"))
      (node (ref "Q112") (pin "3") (pinfunction "E_3") (pintype "passive"))
      (node (ref "Q114") (pin "3") (pinfunction "E_3") (pintype "passive"))
      (node (ref "Q120") (pin "E") (pinfunction "E_E") (pintype "passive"))
      (node (ref "Q122") (pin "E") (pinfunction "E_E") (pintype "passive"))
      (node (ref "R124") (pin "1") (pinfunction "1_1") (pintype "passive"))
      (node (ref "R126") (pin "1") (pinfunction "1_1") (pintype "passive"))
      (node (ref "R201") (pin "1") (pinfunction "1_1") (pintype "passive"))
      (node (ref "SWT_OUT") (pin "2") (pinfunction "1_2") (pintype "passive"))
    )
    (net (code "57") (name "unconnected-(KK101-K-PadK1)") (class "Default")
      (node (ref "KK101") (pin "K1") (pinfunction "K_K1") (pintype "passive"))
    )
    (net (code "58") (name "unconnected-(KK101-K-PadK2)") (class "Default")
      (node (ref "KK101") (pin "K2") (pinfunction "K_K2") (pintype "passive"))
    )
    (net (code "59") (name "unconnected-(KK102-K-PadK1)") (class "Default")
      (node (ref "KK102") (pin "K1") (pinfunction "K_K1") (pintype "passive"))
    )
    (net (code "60") (name "unconnected-(KK102-K-PadK2)") (class "Default")
      (node (ref "KK102") (pin "K2") (pinfunction "K_K2") (pintype "passive"))
    )
    (net (code "61") (name "unconnected-(KK103-K-PadK1)") (class "Default")
      (node (ref "KK103") (pin "K1") (pinfunction "K_K1") (pintype "passive"))
    )
    (net (code "62") (name "unconnected-(KK103-K-PadK2)") (class "Default")
      (node (ref "KK103") (pin "K2") (pinfunction "K_K2") (pintype "passive"))
    )
    (net (code "63") (name "unconnected-(KK104-K-PadK1)") (class "Default")
      (node (ref "KK104") (pin "K1") (pinfunction "K_K1") (pintype "passive"))
    )
    (net (code "64") (name "unconnected-(KK104-K-PadK2)") (class "Default")
      (node (ref "KK104") (pin "K2") (pinfunction "K_K2") (pintype "passive"))
    )
  )
)
